# Power.net
KiCad netlist of a schematic drawn in Altium Designer
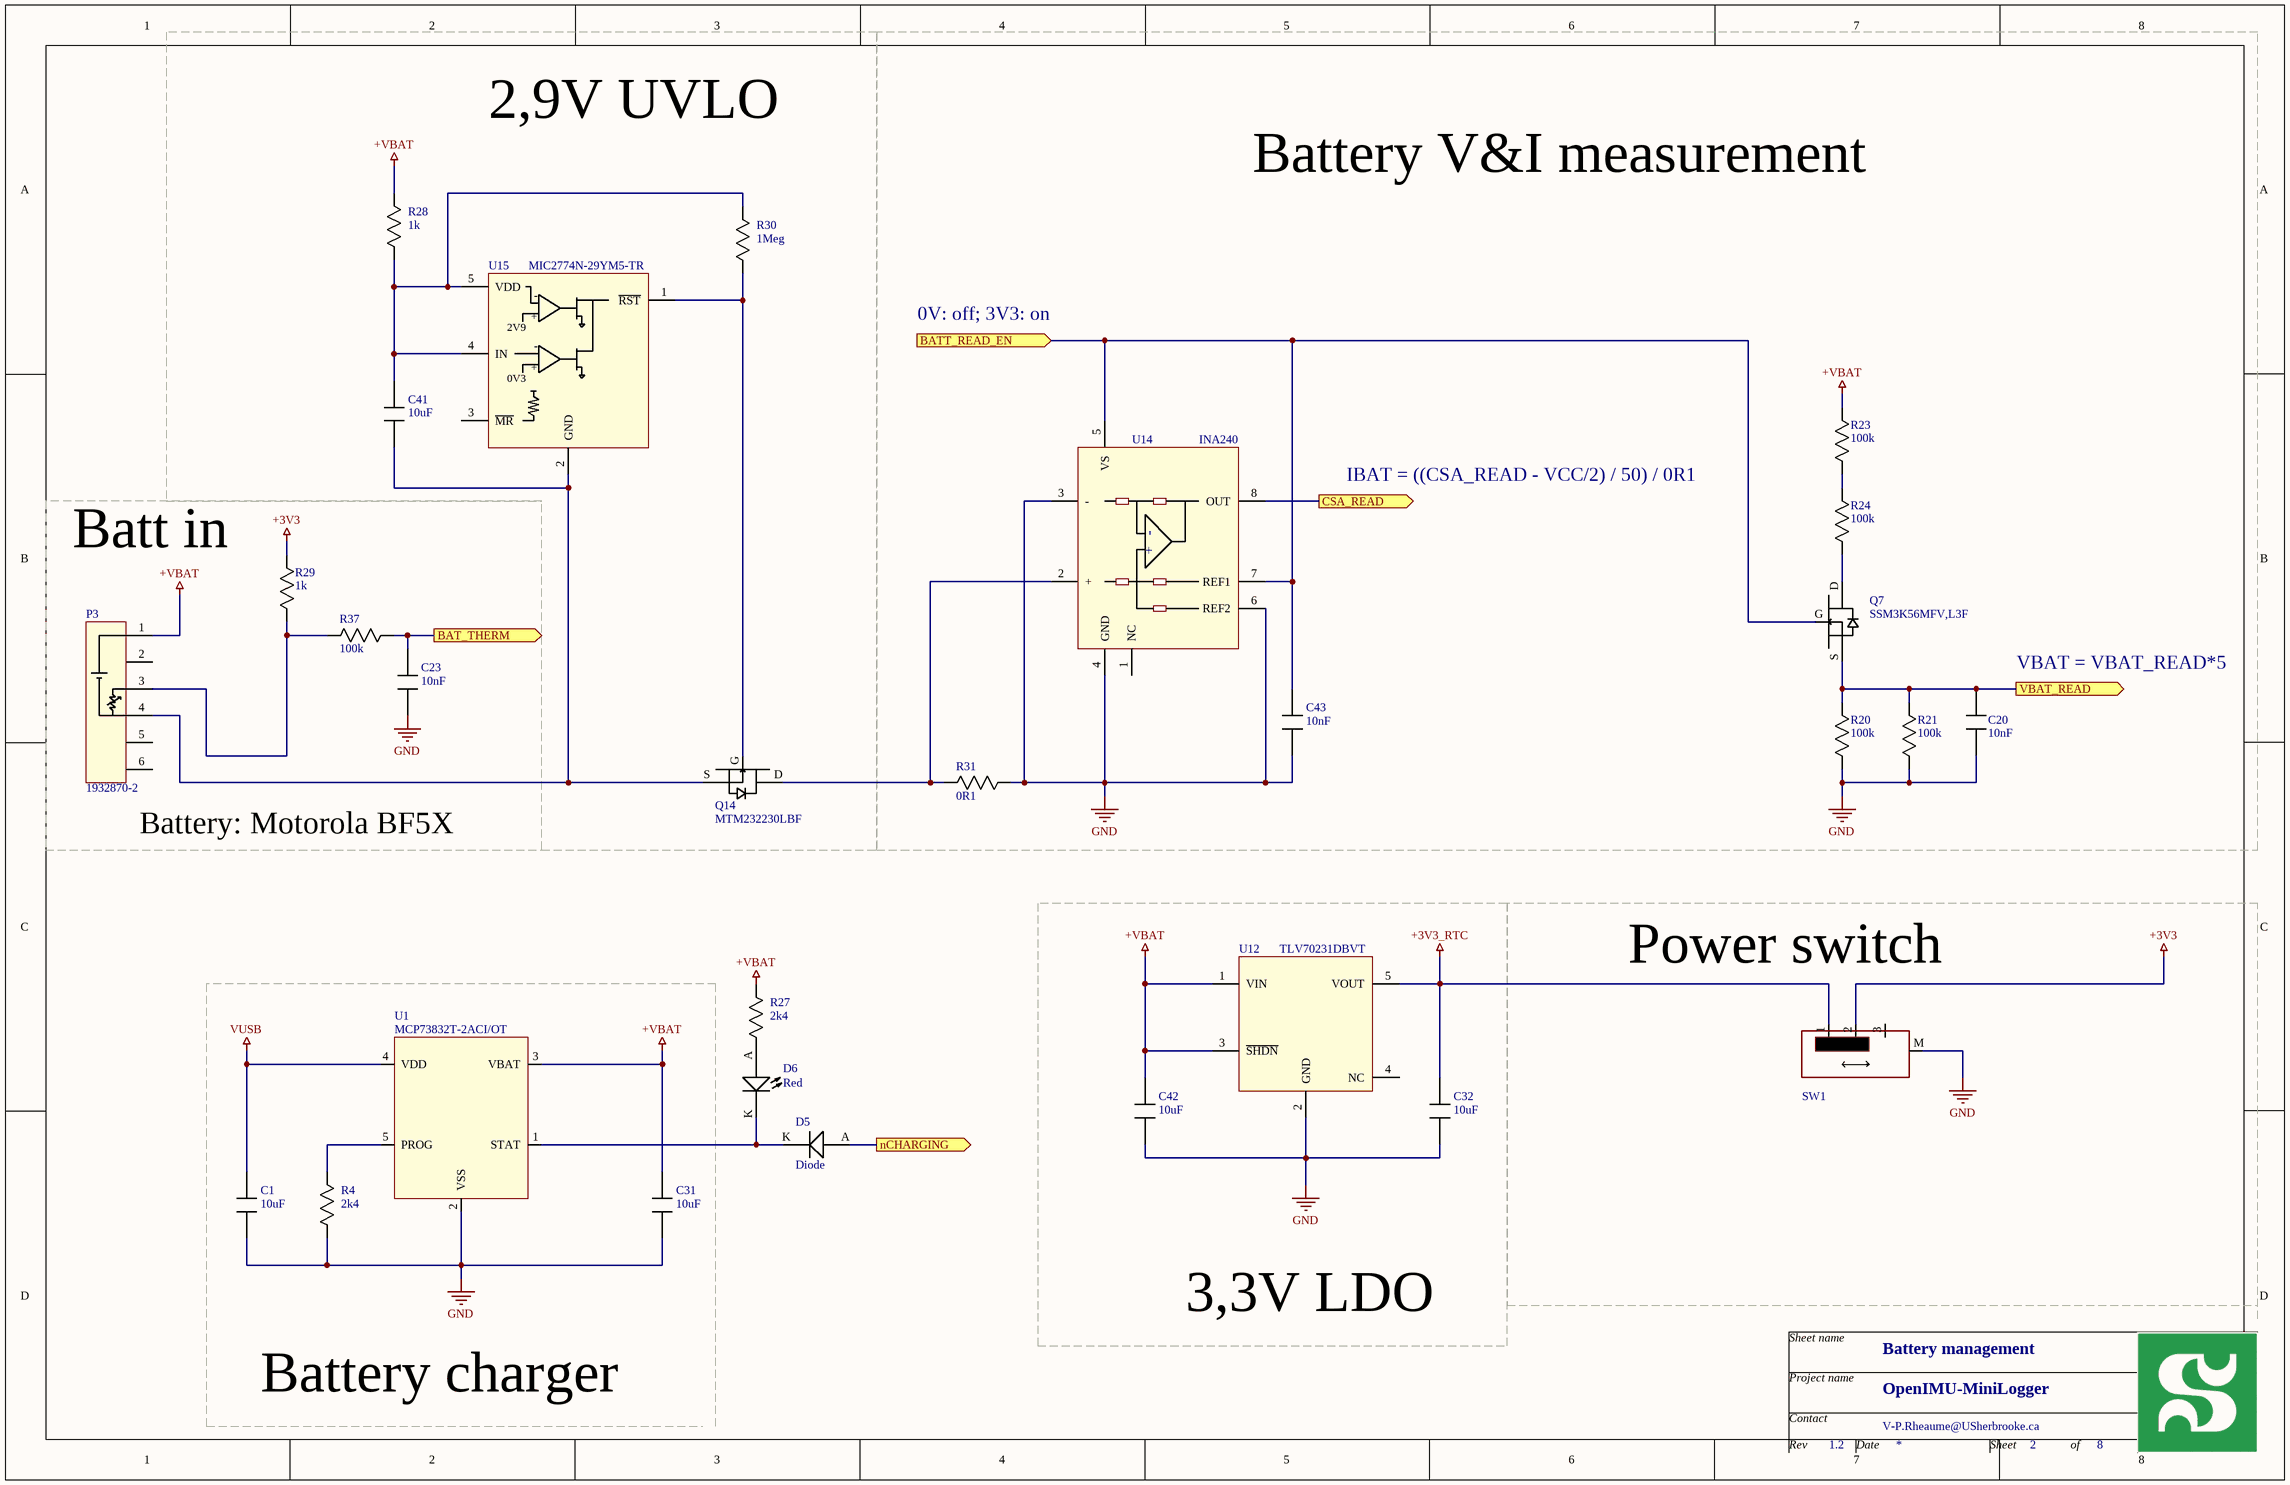
[diagram p0: Power.SchDoc]

(export (version "E")
  (design (tool "Eeschema 10.0.6"))
  (components
    (comp (ref "C1")
      (value "10uF")
      (footprint "0603")
      (description "Capacitor")
      (fields (field (name "MFG") "Murata"))
      (libsource (lib "INTER_2014") (part "Capacitor"))
    )
    (comp (ref "C20")
      (value "10nF")
      (footprint "0603")
      (description "Capacitor")
      (fields (field (name "MFG") "Wurth"))
      (libsource (lib "INTER_2014") (part "Capacitor"))
    )
    (comp (ref "C23")
      (value "10nF")
      (footprint "0603")
      (description "Capacitor")
      (fields (field (name "MFG") "Wurth"))
      (libsource (lib "INTER_2014") (part "Capacitor"))
    )
    (comp (ref "C31")
      (value "10uF")
      (footprint "0603")
      (description "Capacitor")
      (fields (field (name "MFG") "Murata"))
      (libsource (lib "INTER_2014") (part "Capacitor"))
    )
    (comp (ref "C32")
      (value "10uF")
      (footprint "0603")
      (description "Capacitor")
      (fields (field (name "MFG") "Murata"))
      (libsource (lib "INTER_2014") (part "Capacitor"))
    )
    (comp (ref "C41")
      (value "10uF")
      (footprint "0603")
      (description "Capacitor")
      (fields (field (name "MFG") "Murata"))
      (libsource (lib "INTER_2014") (part "Capacitor"))
    )
    (comp (ref "C42")
      (value "10uF")
      (footprint "0603")
      (description "Capacitor")
      (fields (field (name "MFG") "Murata"))
      (libsource (lib "INTER_2014") (part "Capacitor"))
    )
    (comp (ref "C43")
      (value "10nF")
      (footprint "0603")
      (description "Capacitor")
      (fields (field (name "MFG") "Wurth"))
      (libsource (lib "INTER_2014") (part "Capacitor"))
    )
    (comp (ref "D5")
      (value "Diode")
      (footprint "DIODE_SOD523")
      (fields (field (name "MFG") "MCC"))
      (libsource (lib "INTER_2014") (part "Diode"))
    )
    (comp (ref "D6")
      (value "Red")
      (footprint "0805_LED")
      (description "LED")
      (fields (field (name "MFG") "Wurth") (field (name "Comment") "Diode_LED"))
      (libsource (lib "INTER_2014") (part "Diode_LED"))
    )
    (comp (ref "P3")
      (value "CON6_FBIS2")
      (footprint "CONN6_FBIS2_V")
      (description "6-pins for Motorola?")
      (fields (field (name "MFG") "TE") (field (name "MFG_PN") "1932870-2"))
      (libsource (lib "INTER_2014") (part "CON6_FBIS2"))
    )
    (comp (ref "Q7")
      (value "MOSFET_N_GDS")
      (footprint "SOT723")
      (description "NMOS")
      (fields (field (name "MFG") "Toshiba") (field (name "MFG_PN") "SSM3K56MFV,L3F"))
      (libsource (lib "INTER_2014") (part "MOSFET_N_GDS"))
    )
    (comp (ref "Q14")
      (value "MOSFET_N_GDS")
      (footprint "SC70_GDS")
      (description "NMOS")
      (fields (field (name "MFG") "Panasonic") (field (name "MFG_PN") "MTM232230LBF"))
      (libsource (lib "INTER_2014") (part "MOSFET_N_GDS"))
    )
    (comp (ref "R4")
      (value "2k4")
      (footprint "0402")
      (description "Resistor")
      (fields (field (name "MFG") "Yageo"))
      (libsource (lib "INTER_2014") (part "Resistor"))
    )
    (comp (ref "R20")
      (value "100k")
      (footprint "0402")
      (description "Resistor")
      (fields (field (name "MFG") "Yageo"))
      (libsource (lib "INTER_2014") (part "Resistor"))
    )
    (comp (ref "R21")
      (value "100k")
      (footprint "0402")
      (description "Resistor")
      (fields (field (name "MFG") "Yageo"))
      (libsource (lib "INTER_2014") (part "Resistor"))
    )
    (comp (ref "R23")
      (value "100k")
      (footprint "0402")
      (description "Resistor")
      (fields (field (name "MFG") "Yageo"))
      (libsource (lib "INTER_2014") (part "Resistor"))
    )
    (comp (ref "R24")
      (value "100k")
      (footprint "0402")
      (description "Resistor")
      (fields (field (name "MFG") "Yageo"))
      (libsource (lib "INTER_2014") (part "Resistor"))
    )
    (comp (ref "R27")
      (value "2k4")
      (footprint "0402")
      (description "Resistor")
      (fields (field (name "MFG") "Yageo"))
      (libsource (lib "INTER_2014") (part "Resistor"))
    )
    (comp (ref "R28")
      (value "1k")
      (footprint "0603")
      (description "Resistor")
      (fields (field (name "MFG") "Yageo"))
      (libsource (lib "INTER_2014") (part "Resistor"))
    )
    (comp (ref "R29")
      (value "1k")
      (footprint "0402")
      (description "Resistor")
      (fields (field (name "MFG") "TE"))
      (libsource (lib "INTER_2014") (part "Resistor"))
    )
    (comp (ref "R30")
      (value "1Meg")
      (footprint "0603")
      (description "Resistor")
      (fields (field (name "MFG") "Stackpole"))
      (libsource (lib "INTER_2014") (part "Resistor"))
    )
    (comp (ref "R31")
      (value "0R1")
      (footprint "0603")
      (description "Resistor")
      (fields (field (name "MFG") "TE"))
      (libsource (lib "INTER_2014") (part "Resistor"))
    )
    (comp (ref "R37")
      (value "100k")
      (footprint "0402")
      (description "Resistor")
      (fields (field (name "MFG") "Yageo"))
      (libsource (lib "INTER_2014") (part "Resistor"))
    )
    (comp (ref "SW1")
      (value "Button_Slideswitch_MLL1200S")
      (footprint "SWITCH_ MLL1200S")
      (description "Slide switch")
      (fields (field (name "MFG") "TE"))
      (libsource (lib "INTER_2014") (part "Button_Slideswitch_MLL1200S"))
    )
    (comp (ref "U1")
      (value "MCP73831T-2ACI/OT")
      (footprint "SOT23_5")
      (description "Lithium Ion Battery charger, linear")
      (fields (field (name "MFG") "Microchip") (field (name "MFG_PN") "MCP73832T-2ACI/OT"))
      (libsource (lib "INTER_2014") (part "MCP73831T-2ACI/OT"))
    )
    (comp (ref "U12")
      (value "AP2112K-3.3TRG1")
      (footprint "SOT23_5")
      (description "Linear voltage regulator")
      (fields (field (name "MFG") "TI") (field (name "MFG_PN") "TLV70231DBVT"))
      (libsource (lib "INTER_2014") (part "AP2112K-3.3TRG1"))
    )
    (comp (ref "U14")
      (value "INA240")
      (footprint "TSSOP8")
      (fields (field (name "MFG") "Texas Instruments"))
      (libsource (lib "INTER_2014") (part "INA240"))
    )
    (comp (ref "U15")
      (value "MIC2774N-29YM5-TR")
      (footprint "SOT23_5")
      (description "Voltage supervisor and power-on timer, dual")
      (fields (field (name "MFG") "Micrel"))
      (libsource (lib "INTER_2014") (part "MIC2774N-29YM5-TR"))
    )
  )
  (nets
    (net (code "1") (name "+3V3") (class "Default")
      (node (ref "R29") (pin "2") (pintype "passive"))
      (node (ref "SW1") (pin "2") (pintype "passive"))
    )
    (net (code "2") (name "+3V3_RTC") (class "Default")
      (node (ref "C32") (pin "2") (pintype "passive"))
      (node (ref "SW1") (pin "1") (pintype "passive"))
      (node (ref "U12") (pin "5") (pinfunction "VOUT_5") (pintype "passive"))
    )
    (net (code "3") (name "+VBAT") (class "Default")
      (node (ref "C31") (pin "2") (pintype "passive"))
      (node (ref "C42") (pin "2") (pintype "passive"))
      (node (ref "P3") (pin "1") (pintype "passive"))
      (node (ref "R23") (pin "2") (pintype "passive"))
      (node (ref "R27") (pin "1") (pintype "passive"))
      (node (ref "R28") (pin "1") (pintype "passive"))
      (node (ref "U1") (pin "3") (pinfunction "VBAT_3") (pintype "passive"))
      (node (ref "U12") (pin "1") (pinfunction "VIN_1") (pintype "passive"))
      (node (ref "U12") (pin "3") (pinfunction "~{SHDN}_3") (pintype "passive"))
    )
    (net (code "4") (name "/BATT_READ_EN") (class "Default")
      (node (ref "C43") (pin "2") (pintype "passive"))
      (node (ref "Q7") (pin "G") (pintype "passive"))
      (node (ref "U14") (pin "5") (pinfunction "VS_5") (pintype "passive"))
      (node (ref "U14") (pin "7") (pinfunction "REF1_7") (pintype "passive"))
    )
    (net (code "5") (name "/BAT_THERM") (class "Default")
      (node (ref "C23") (pin "2") (pintype "passive"))
      (node (ref "R37") (pin "1") (pintype "passive"))
    )
    (net (code "6") (name "/CSA_READ") (class "Default")
      (node (ref "U14") (pin "8") (pinfunction "OUT_8") (pintype "passive"))
    )
    (net (code "7") (name "/VBAT_READ") (class "Default")
      (node (ref "C20") (pin "2") (pintype "passive"))
      (node (ref "Q7") (pin "S") (pintype "passive"))
      (node (ref "R20") (pin "2") (pintype "passive"))
      (node (ref "R21") (pin "2") (pintype "passive"))
    )
    (net (code "8") (name "/nCHARGING") (class "Default") (node (ref "D5") (pin "A") (pintype "passive")))
    (net (code "9") (name "GND") (class "Default")
      (node (ref "C1") (pin "1") (pintype "passive"))
      (node (ref "C20") (pin "1") (pintype "passive"))
      (node (ref "C23") (pin "1") (pintype "passive"))
      (node (ref "C31") (pin "1") (pintype "passive"))
      (node (ref "C32") (pin "1") (pintype "passive"))
      (node (ref "C42") (pin "1") (pintype "passive"))
      (node (ref "C43") (pin "1") (pintype "passive"))
      (node (ref "R20") (pin "1") (pintype "passive"))
      (node (ref "R21") (pin "1") (pintype "passive"))
      (node (ref "R31") (pin "2") (pintype "passive"))
      (node (ref "R4") (pin "2") (pintype "passive"))
      (node (ref "SW1") (pin "M") (pintype "passive"))
      (node (ref "U1") (pin "2") (pinfunction "VSS_2") (pintype "passive"))
      (node (ref "U12") (pin "2") (pinfunction "GND_2") (pintype "passive"))
      (node (ref "U14") (pin "3") (pinfunction "-_3") (pintype "passive"))
      (node (ref "U14") (pin "4") (pinfunction "GND_4") (pintype "passive"))
      (node (ref "U14") (pin "6") (pinfunction "REF2_6") (pintype "passive"))
    )
    (net (code "10") (name "Net-(D6-PadA)") (class "Default")
      (node (ref "D6") (pin "A") (pintype "passive"))
      (node (ref "R27") (pin "2") (pintype "passive"))
    )
    (net (code "11") (name "Net-(P3--)") (class "Default")
      (node (ref "C41") (pin "1") (pintype "passive"))
      (node (ref "P3") (pin "4") (pinfunction "-_4") (pintype "passive"))
      (node (ref "Q14") (pin "S") (pintype "passive"))
      (node (ref "U15") (pin "2") (pinfunction "GND_2") (pintype "passive"))
    )
    (net (code "12") (name "Net-(P3-Pad3)") (class "Default")
      (node (ref "P3") (pin "3") (pintype "passive"))
      (node (ref "R29") (pin "1") (pintype "passive"))
      (node (ref "R37") (pin "2") (pintype "passive"))
    )
    (net (code "13") (name "Net-(Q7-PadD)") (class "Default")
      (node (ref "Q7") (pin "D") (pintype "passive"))
      (node (ref "R24") (pin "1") (pintype "passive"))
    )
    (net (code "14") (name "Net-(R23-Pad1)") (class "Default")
      (node (ref "R23") (pin "1") (pintype "passive"))
      (node (ref "R24") (pin "2") (pintype "passive"))
    )
    (net (code "15") (name "Net-(U1-PROG)") (class "Default")
      (node (ref "R4") (pin "1") (pintype "passive"))
      (node (ref "U1") (pin "5") (pinfunction "PROG_5") (pintype "passive"))
    )
    (net (code "16") (name "Net-(U1-STAT)") (class "Default")
      (node (ref "D5") (pin "K") (pintype "passive"))
      (node (ref "D6") (pin "K") (pintype "passive"))
      (node (ref "U1") (pin "1") (pinfunction "STAT_1") (pintype "passive"))
    )
    (net (code "17") (name "Net-(U14-+)") (class "Default")
      (node (ref "Q14") (pin "D") (pintype "passive"))
      (node (ref "R31") (pin "1") (pintype "passive"))
      (node (ref "U14") (pin "2") (pinfunction "+_2") (pintype "passive"))
    )
    (net (code "18") (name "Net-(U15-IN)") (class "Default")
      (node (ref "C41") (pin "2") (pintype "passive"))
      (node (ref "R28") (pin "2") (pintype "passive"))
      (node (ref "R30") (pin "1") (pintype "passive"))
      (node (ref "U15") (pin "4") (pinfunction "IN_4") (pintype "passive"))
      (node (ref "U15") (pin "5") (pinfunction "VDD_5") (pintype "passive"))
    )
    (net (code "19") (name "Net-(U15-~{RST})") (class "Default")
      (node (ref "Q14") (pin "G") (pintype "passive"))
      (node (ref "R30") (pin "2") (pintype "passive"))
      (node (ref "U15") (pin "1") (pinfunction "~{RST}_1") (pintype "open_collector"))
    )
    (net (code "20") (name "VUSB") (class "Default")
      (node (ref "C1") (pin "2") (pintype "passive"))
      (node (ref "U1") (pin "4") (pinfunction "VDD_4") (pintype "passive"))
    )
    (net (code "21") (name "unconnected-(P3-Pad2)") (class "Default")
      (node (ref "P3") (pin "2") (pintype "passive"))
    )
    (net (code "22") (name "unconnected-(P3-Pad5)") (class "Default")
      (node (ref "P3") (pin "5") (pintype "passive"))
    )
    (net (code "23") (name "unconnected-(P3-Pad6)") (class "Default")
      (node (ref "P3") (pin "6") (pintype "passive"))
    )
    (net (code "24") (name "unconnected-(SW1-Pad3)") (class "Default")
      (node (ref "SW1") (pin "3") (pintype "passive"))
    )
    (net (code "25") (name "unconnected-(U12-NC-Pad4)") (class "Default")
      (node (ref "U12") (pin "4") (pinfunction "NC_4") (pintype "passive"))
    )
    (net (code "26") (name "unconnected-(U14-NC-Pad1)") (class "Default")
      (node (ref "U14") (pin "1") (pinfunction "NC_1") (pintype "passive"))
    )
    (net (code "27") (name "unconnected-(U15-~{MR}-Pad3)") (class "Default")
      (node (ref "U15") (pin "3") (pinfunction "~{MR}_3") (pintype "passive"))
    )
  )
)
